# TBA820-Module.net
KiCad netlist of a schematic drawn in EAGLE
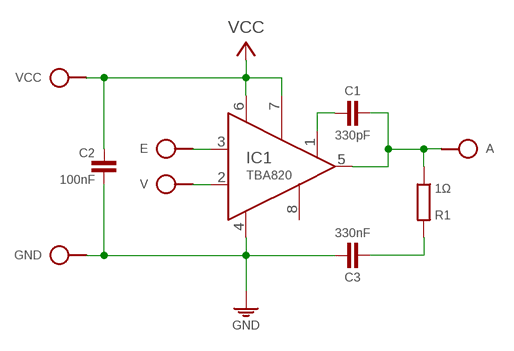
[diagram p0: schematic, sheet 1]

(export (version "E")
  (design (tool "Eeschema 10.0.6"))
  (components
    (comp (ref "A")
      (value "SPAD")
      (footprint "eagle-import:SPAD")
      (libsource (lib "eagle-import") (part "SPAD"))
    )
    (comp (ref "C1")
      (value "330pF")
      (footprint "eagle-import:C050-020X044")
      (libsource (lib "eagle-import") (part "C-H050-020X044"))
    )
    (comp (ref "C2")
      (value "100nF")
      (footprint "eagle-import:C050-025X075")
      (libsource (lib "eagle-import") (part "C050-025X075"))
    )
    (comp (ref "C3")
      (value "330nF")
      (footprint "eagle-import:C050-020X044")
      (libsource (lib "eagle-import") (part "C-H050-020X044"))
    )
    (comp (ref "E")
      (value "SPAD")
      (footprint "eagle-import:SPAD")
      (libsource (lib "eagle-import") (part "SPAD"))
    )
    (comp (ref "GND")
      (value "SPAD")
      (footprint "eagle-import:SPAD")
      (libsource (lib "eagle-import") (part "SPAD"))
    )
    (comp (ref "IC1")
      (value "TBA820")
      (footprint "eagle-import:DIL08")
      (libsource (lib "eagle-import") (part "TBA820"))
    )
    (comp (ref "R1")
      (value "1Ω")
      (footprint "eagle-import:0204_10")
      (libsource (lib "eagle-import") (part "R0204/10"))
    )
    (comp (ref "V")
      (value "SPAD")
      (footprint "eagle-import:SPAD")
      (libsource (lib "eagle-import") (part "SPAD"))
    )
    (comp (ref "VCC")
      (value "SPAD")
      (footprint "eagle-import:SPAD")
      (libsource (lib "eagle-import") (part "SPAD"))
    )
  )
  (nets
    (net (code "1") (name "GND") (class "Default")
      (node (ref "C2") (pin "2") (pinfunction "2_2") (pintype "passive"))
      (node (ref "C3") (pin "2") (pinfunction "2_2") (pintype "passive"))
      (node (ref "GND") (pin "1") (pinfunction "P$1_1") (pintype "passive"))
      (node (ref "IC1") (pin "4") (pinfunction "GND_4") (pintype "power_in"))
    )
    (net (code "2") (name "Net-(A-P$1)") (class "Default")
      (node (ref "A") (pin "1") (pinfunction "P$1_1") (pintype "passive"))
      (node (ref "C1") (pin "2") (pinfunction "2_2") (pintype "passive"))
      (node (ref "IC1") (pin "5") (pinfunction "OUT_5") (pintype "output"))
      (node (ref "R1") (pin "2") (pinfunction "1_2") (pintype "passive"))
    )
    (net (code "3") (name "Net-(E-P$1)") (class "Default")
      (node (ref "E") (pin "1") (pinfunction "P$1_1") (pintype "passive"))
      (node (ref "IC1") (pin "3") (pinfunction "INPUT_3") (pintype "input"))
    )
    (net (code "4") (name "Net-(IC1-FREQ)") (class "Default")
      (node (ref "C1") (pin "1") (pinfunction "1_1") (pintype "passive"))
      (node (ref "IC1") (pin "1") (pinfunction "FREQ_1") (pintype "input"))
    )
    (net (code "5") (name "Net-(IC1-GAIN)") (class "Default")
      (node (ref "IC1") (pin "2") (pinfunction "GAIN_2") (pintype "input"))
      (node (ref "V") (pin "1") (pinfunction "P$1_1") (pintype "passive"))
    )
    (net (code "6") (name "Net-(R1-2)") (class "Default")
      (node (ref "C3") (pin "1") (pinfunction "1_1") (pintype "passive"))
      (node (ref "R1") (pin "1") (pinfunction "2_1") (pintype "passive"))
    )
    (net (code "7") (name "VCC") (class "Default")
      (node (ref "C2") (pin "1") (pinfunction "1_1") (pintype "passive"))
      (node (ref "IC1") (pin "6") (pinfunction "VCC_6") (pintype "power_in"))
      (node (ref "IC1") (pin "7") (pinfunction "BOOT_7") (pintype "input"))
      (node (ref "VCC") (pin "1") (pinfunction "P$1_1") (pintype "passive"))
    )
    (net (code "8") (name "unconnected-(IC1-RIPPLE-Pad8)") (class "Default")
      (node (ref "IC1") (pin "8") (pinfunction "RIPPLE_8") (pintype "input"))
    )
  )
)
